# timer.net
KiCad netlist of a schematic drawn in EAGLE
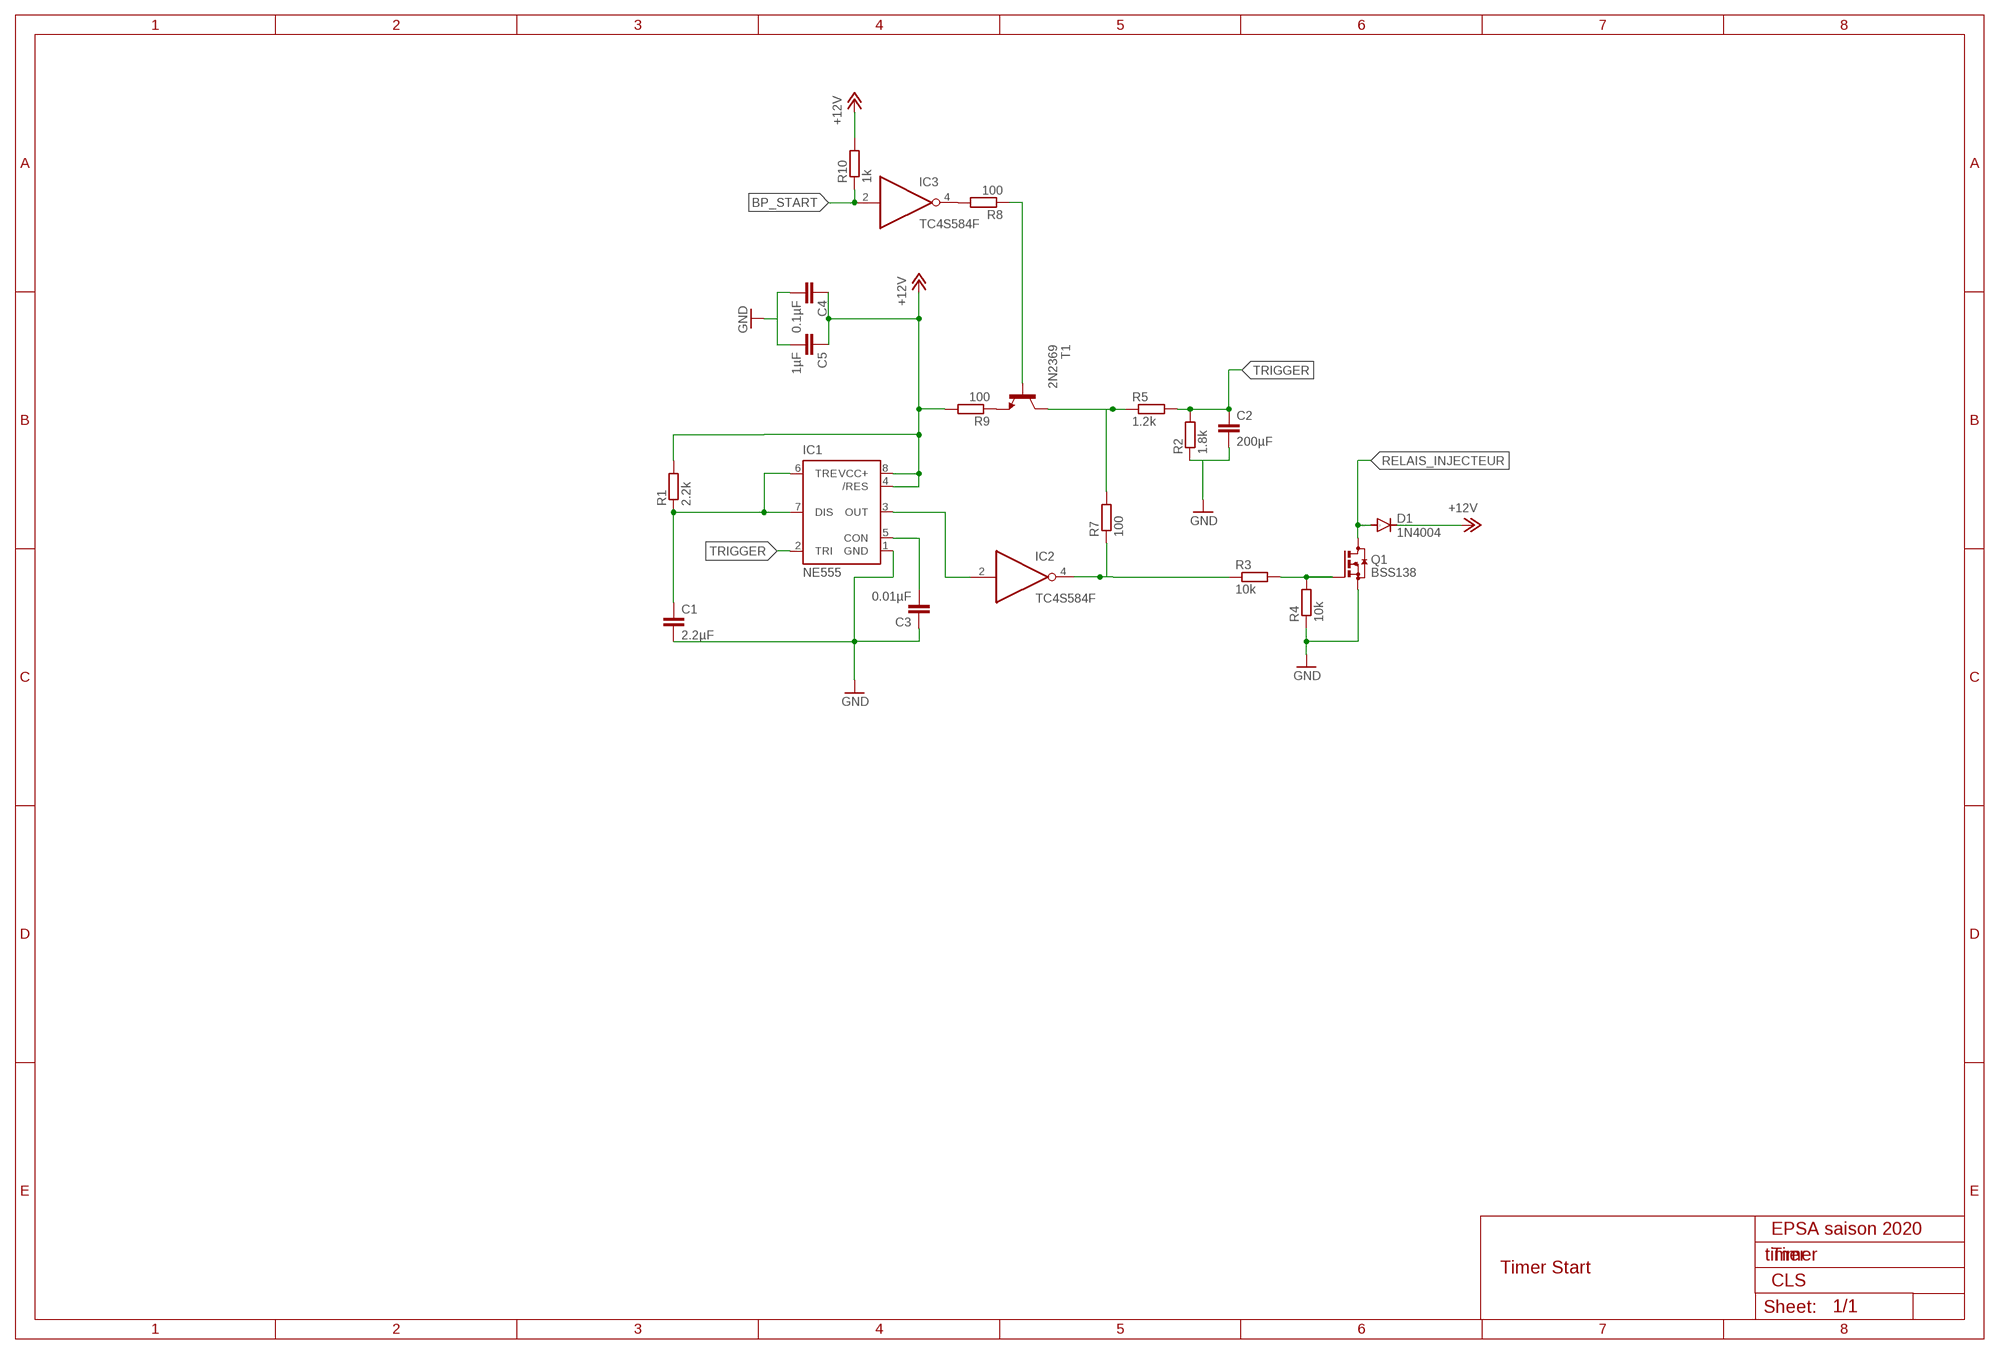
[diagram p0: schematic, sheet 1]

(export (version "E")
  (design (tool "Eeschema 10.0.6"))
  (components
    (comp (ref "C1")
      (value "2.2µF")
      (footprint "eagle-import:C0805")
      (libsource (lib "eagle-import") (part "C-EUC0805"))
    )
    (comp (ref "C2")
      (value "200µF")
      (footprint "eagle-import:C0805")
      (libsource (lib "eagle-import") (part "C-EUC0805"))
    )
    (comp (ref "C3")
      (value "0.01µF")
      (footprint "eagle-import:C0805")
      (libsource (lib "eagle-import") (part "C-EUC0805"))
    )
    (comp (ref "C4")
      (value "0.1µF")
      (footprint "eagle-import:C0805")
      (libsource (lib "eagle-import") (part "C-EUC0805"))
    )
    (comp (ref "C5")
      (value "1µF")
      (footprint "eagle-import:C0805")
      (libsource (lib "eagle-import") (part "C-EUC0805"))
    )
    (comp (ref "D1")
      (value "1N4004")
      (footprint "eagle-import:DO41-10")
      (libsource (lib "eagle-import") (part "1N4004"))
    )
    (comp (ref "IC1")
      (value "NE555")
      (footprint "eagle-import:DIL-08")
      (fields (field (name "MF") "Arrow Electronics") (field (name "MPN") "NE555N"))
      (libsource (lib "eagle-import") (part "NE555"))
    )
    (comp (ref "IC2")
      (value "TC4S584F")
      (footprint "eagle-import:SOT23-5")
      (libsource (lib "eagle-import") (part "741G04DBVAHC"))
    )
    (comp (ref "IC3")
      (value "TC4S584F")
      (footprint "eagle-import:SOT23-5")
      (libsource (lib "eagle-import") (part "741G04DBVAHC"))
    )
    (comp (ref "Q1")
      (value "BSS138")
      (footprint "eagle-import:SOT23")
      (libsource (lib "eagle-import") (part "BSS123"))
    )
    (comp (ref "R1")
      (value "2.2k")
      (footprint "eagle-import:R0805")
      (libsource (lib "eagle-import") (part "R-EU_R0805"))
    )
    (comp (ref "R2")
      (value "1.8k")
      (footprint "eagle-import:R0805")
      (libsource (lib "eagle-import") (part "R-EU_R0805"))
    )
    (comp (ref "R3")
      (value "10k")
      (footprint "eagle-import:R0805")
      (libsource (lib "eagle-import") (part "R-EU_R0805"))
    )
    (comp (ref "R4")
      (value "10k")
      (footprint "eagle-import:R0805")
      (libsource (lib "eagle-import") (part "R-EU_R0805"))
    )
    (comp (ref "R5")
      (value "1.2k")
      (footprint "eagle-import:R0805")
      (libsource (lib "eagle-import") (part "R-EU_R0805"))
    )
    (comp (ref "R7")
      (value "100")
      (footprint "eagle-import:R0805")
      (libsource (lib "eagle-import") (part "R-EU_R0805"))
    )
    (comp (ref "R8")
      (value "100")
      (footprint "eagle-import:R0805")
      (libsource (lib "eagle-import") (part "R-EU_R0805"))
    )
    (comp (ref "R9")
      (value "100")
      (footprint "eagle-import:R0805")
      (libsource (lib "eagle-import") (part "R-EU_R0805"))
    )
    (comp (ref "R10")
      (value "1k")
      (footprint "eagle-import:R0805")
      (libsource (lib "eagle-import") (part "R-EU_R0805"))
    )
    (comp (ref "T1")
      (value "2N2369")
      (footprint "eagle-import:TO18")
      (libsource (lib "eagle-import") (part "2N2369"))
    )
  )
  (nets
    (net (code "1") (name "+12V") (class "Default")
      (node (ref "C4") (pin "1") (pinfunction "1_1") (pintype "passive"))
      (node (ref "C5") (pin "1") (pinfunction "1_1") (pintype "passive"))
      (node (ref "D1") (pin "C") (pinfunction "C_C") (pintype "passive"))
      (node (ref "IC1") (pin "4") (pinfunction "/RES_4") (pintype "input"))
      (node (ref "IC1") (pin "8") (pinfunction "VCC+_8") (pintype "power_in"))
      (node (ref "R1") (pin "2") (pinfunction "2_2") (pintype "passive"))
      (node (ref "R10") (pin "2") (pinfunction "2_2") (pintype "passive"))
      (node (ref "R9") (pin "2") (pinfunction "2_2") (pintype "passive"))
    )
    (net (code "2") (name "BP_START") (class "Default")
      (node (ref "IC3") (pin "2") (pinfunction "I_2") (pintype "input"))
      (node (ref "R10") (pin "1") (pinfunction "1_1") (pintype "passive"))
    )
    (net (code "3") (name "GND") (class "Default")
      (node (ref "C1") (pin "2") (pinfunction "2_2") (pintype "passive"))
      (node (ref "C3") (pin "1") (pinfunction "1_1") (pintype "passive"))
      (node (ref "IC1") (pin "1") (pinfunction "GND_1") (pintype "power_in"))
      (node (ref "Q1") (pin "2") (pinfunction "S_2") (pintype "passive"))
      (node (ref "R4") (pin "1") (pinfunction "1_1") (pintype "passive"))
    )
    (net (code "4") (name "Net-(C2-Pad2)") (class "Default")
      (node (ref "C2") (pin "2") (pinfunction "2_2") (pintype "passive"))
      (node (ref "R2") (pin "1") (pinfunction "1_1") (pintype "passive"))
    )
    (net (code "5") (name "Net-(C4-Pad2)") (class "Default")
      (node (ref "C4") (pin "2") (pinfunction "2_2") (pintype "passive"))
      (node (ref "C5") (pin "2") (pinfunction "2_2") (pintype "passive"))
    )
    (net (code "6") (name "Net-(IC1-CON)") (class "Default")
      (node (ref "C3") (pin "2") (pinfunction "2_2") (pintype "passive"))
      (node (ref "IC1") (pin "5") (pinfunction "CON_5") (pintype "input"))
    )
    (net (code "7") (name "Net-(IC1-DIS)") (class "Default")
      (node (ref "C1") (pin "1") (pinfunction "1_1") (pintype "passive"))
      (node (ref "IC1") (pin "6") (pinfunction "TRE_6") (pintype "input"))
      (node (ref "IC1") (pin "7") (pinfunction "DIS_7") (pintype "input"))
      (node (ref "R1") (pin "1") (pinfunction "1_1") (pintype "passive"))
    )
    (net (code "8") (name "Net-(IC1-OUT)") (class "Default")
      (node (ref "IC1") (pin "3") (pinfunction "OUT_3") (pintype "output"))
      (node (ref "IC2") (pin "2") (pinfunction "I_2") (pintype "input"))
    )
    (net (code "9") (name "Net-(IC2A-O)") (class "Default")
      (node (ref "IC2") (pin "4") (pinfunction "O_4") (pintype "output"))
      (node (ref "R3") (pin "1") (pinfunction "1_1") (pintype "passive"))
      (node (ref "R7") (pin "1") (pinfunction "1_1") (pintype "passive"))
    )
    (net (code "10") (name "Net-(IC3A-O)") (class "Default")
      (node (ref "IC3") (pin "4") (pinfunction "O_4") (pintype "output"))
      (node (ref "R8") (pin "2") (pinfunction "2_2") (pintype "passive"))
    )
    (net (code "11") (name "Net-(Q1-G)") (class "Default")
      (node (ref "Q1") (pin "1") (pinfunction "G_1") (pintype "passive"))
      (node (ref "R3") (pin "2") (pinfunction "2_2") (pintype "passive"))
      (node (ref "R4") (pin "2") (pinfunction "2_2") (pintype "passive"))
    )
    (net (code "12") (name "Net-(T1-B)") (class "Default")
      (node (ref "R8") (pin "1") (pinfunction "1_1") (pintype "passive"))
      (node (ref "T1") (pin "2") (pinfunction "B_2") (pintype "passive"))
    )
    (net (code "13") (name "Net-(T1-C)") (class "Default")
      (node (ref "R5") (pin "1") (pinfunction "1_1") (pintype "passive"))
      (node (ref "R7") (pin "2") (pinfunction "2_2") (pintype "passive"))
      (node (ref "T1") (pin "3") (pinfunction "C_3") (pintype "passive"))
    )
    (net (code "14") (name "Net-(T1-E)") (class "Default")
      (node (ref "R9") (pin "1") (pinfunction "1_1") (pintype "passive"))
      (node (ref "T1") (pin "1") (pinfunction "E_1") (pintype "passive"))
    )
    (net (code "15") (name "RELAIS_INJECTEUR") (class "Default")
      (node (ref "D1") (pin "A") (pinfunction "A_A") (pintype "passive"))
      (node (ref "Q1") (pin "3") (pinfunction "D_3") (pintype "passive"))
    )
    (net (code "16") (name "TRIGGER") (class "Default")
      (node (ref "C2") (pin "1") (pinfunction "1_1") (pintype "passive"))
      (node (ref "IC1") (pin "2") (pinfunction "TRI_2") (pintype "input"))
      (node (ref "R2") (pin "2") (pinfunction "2_2") (pintype "passive"))
      (node (ref "R5") (pin "2") (pinfunction "2_2") (pintype "passive"))
    )
  )
)
